# PG03_SHEET1.net
KiCad netlist of a schematic drawn in Altium Designer
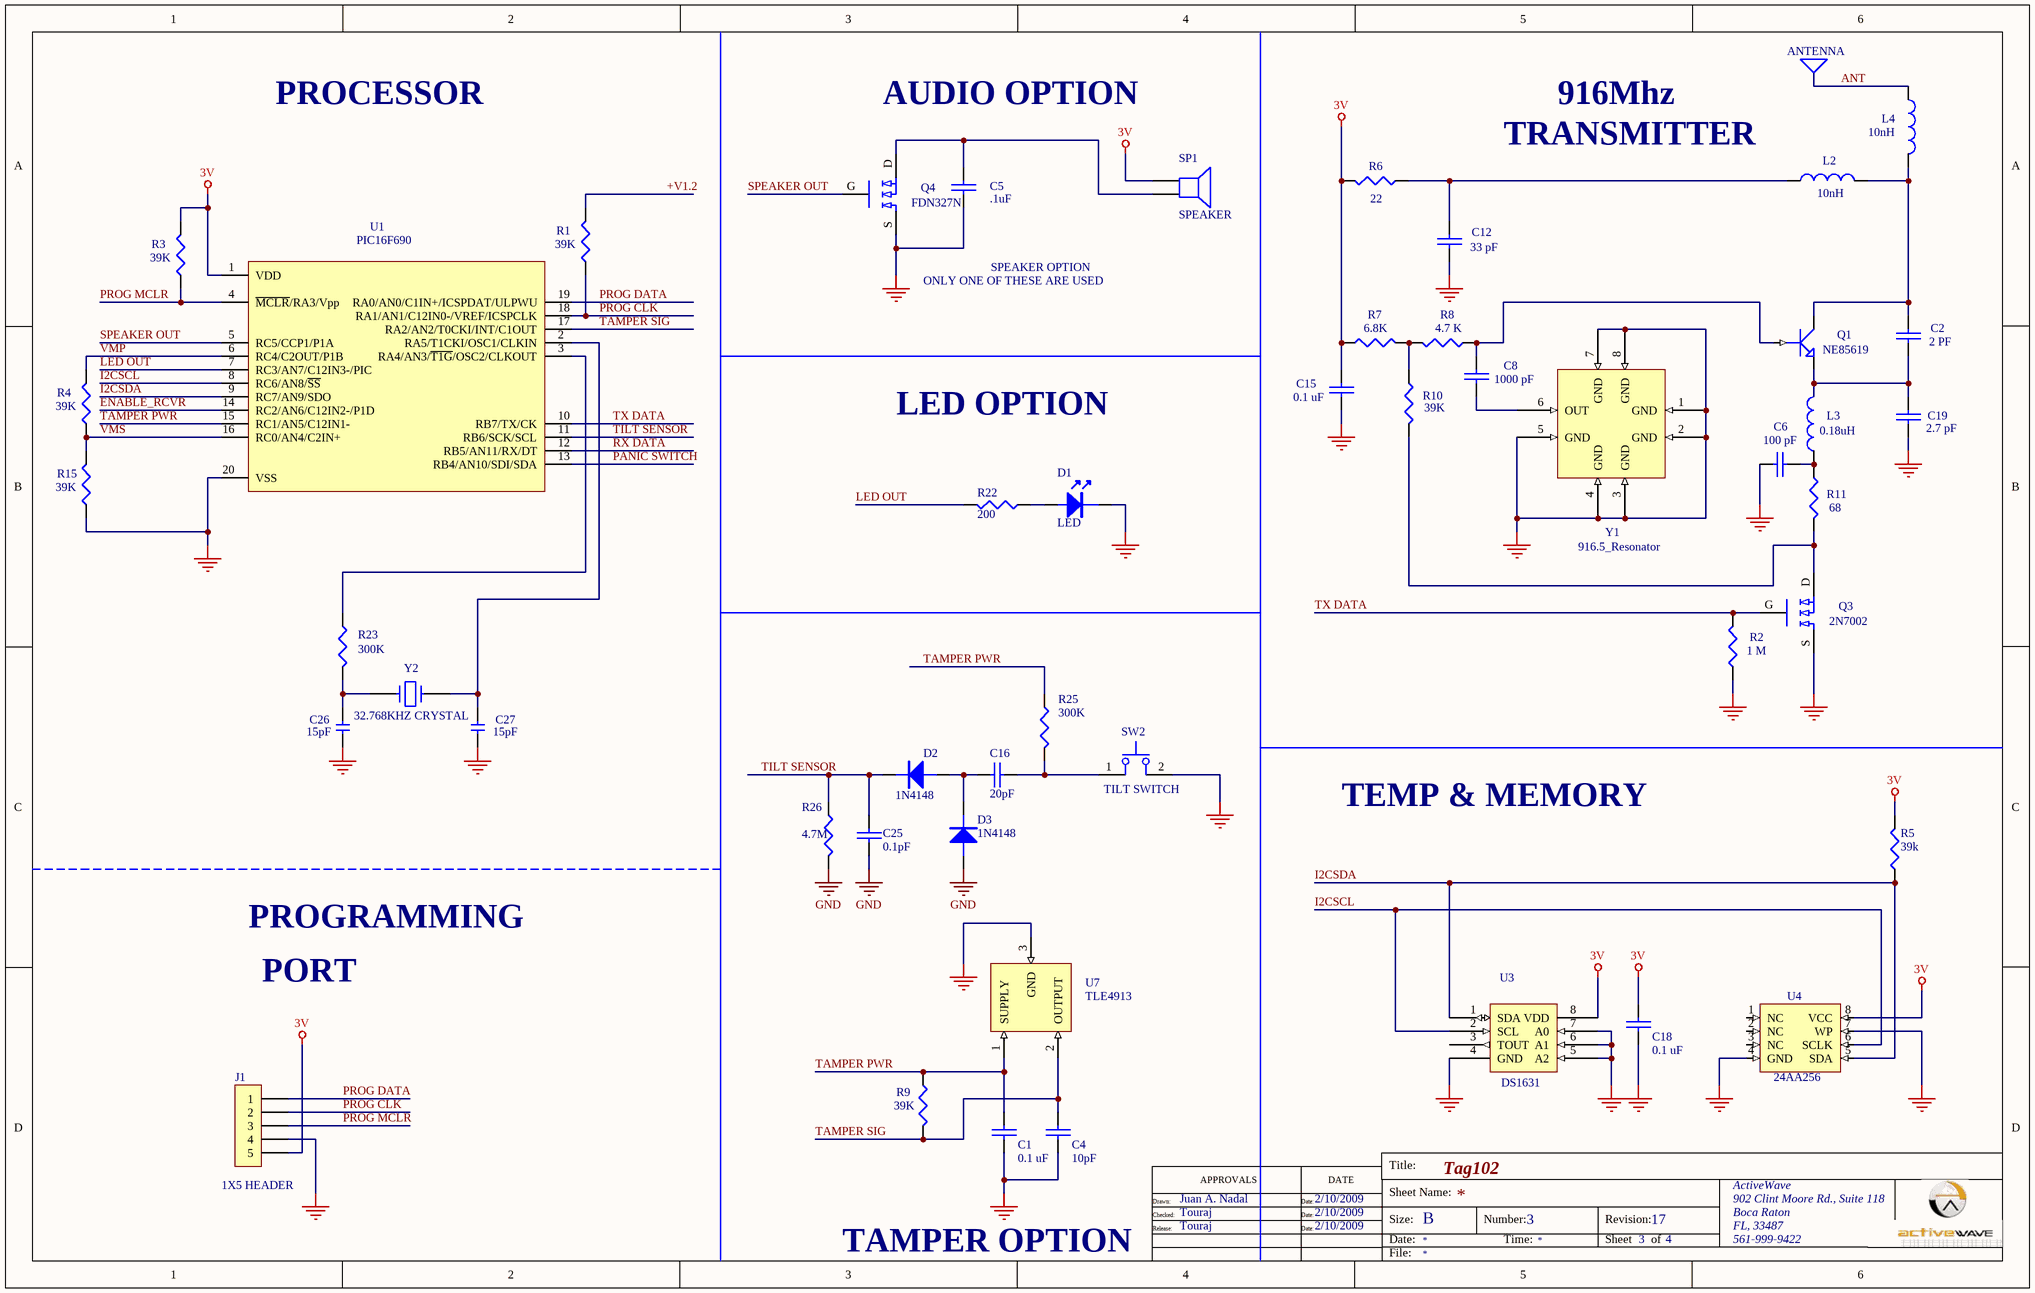
[diagram p0: PG03 SHEET1.schdoc]

(export (version "E")
  (design (tool "Eeschema 10.0.6"))
  (components
    (comp (ref "C1")
      (value "0.1 uF")
      (footprint "0603")
      (description "Capacitor")
      (libsource (lib "*") (part "CAP"))
    )
    (comp (ref "C2")
      (value "2 PF")
      (footprint "0603")
      (description "Capacitor")
      (libsource (lib "*") (part "CAP"))
    )
    (comp (ref "C4")
      (value "10pF")
      (footprint "0603")
      (description "Capacitor")
      (libsource (lib "*") (part "CAP"))
    )
    (comp (ref "C5")
      (value ".1uF")
      (footprint "0603")
      (description "Capacitor")
      (libsource (lib "*") (part "CAP"))
    )
    (comp (ref "C6")
      (value "100 pF")
      (footprint "0603")
      (description "Capacitor")
      (libsource (lib "*") (part "CAP"))
    )
    (comp (ref "C8")
      (value "1000 pF")
      (footprint "0603")
      (description "Capacitor")
      (libsource (lib "*") (part "CAP"))
    )
    (comp (ref "C12")
      (value "33 pF")
      (footprint "0603")
      (description "Capacitor")
      (libsource (lib "*") (part "CAP"))
    )
    (comp (ref "C15")
      (value "0.1 uF")
      (footprint "0603")
      (description "Capacitor")
      (libsource (lib "*") (part "CAP"))
    )
    (comp (ref "C16")
      (value "20pF")
      (footprint "0603")
      (description "Capacitor")
      (libsource (lib "*") (part "CAP"))
    )
    (comp (ref "C18")
      (value "0.1 uF")
      (footprint "0603")
      (description "Capacitor")
      (libsource (lib "*") (part "CAP"))
    )
    (comp (ref "C19")
      (value "2.7 pF")
      (footprint "0603")
      (description "Capacitor")
      (libsource (lib "*") (part "CAP"))
    )
    (comp (ref "C25")
      (value "0.1pF")
      (footprint "0603")
      (description "Capacitor")
      (libsource (lib "*") (part "CAP"))
    )
    (comp (ref "C26") (value "15pF") (footprint "0603") (libsource (lib "*") (part "C")))
    (comp (ref "C27") (value "15pF") (footprint "0603") (libsource (lib "*") (part "C")))
    (comp (ref "D1") (value "LED") (footprint "LED STANLEY H_1105W") (libsource (lib "*") (part "LED")))
    (comp (ref "D2")
      (value "1N4148")
      (footprint "sod123_021405")
      (description "Diode")
      (libsource (lib "*") (part "DIODE"))
    )
    (comp (ref "D3")
      (value "1N4148")
      (footprint "sod123_021405")
      (description "Diode")
      (libsource (lib "*") (part "DIODE"))
    )
    (comp (ref "J1")
      (value "1X5 HEADER")
      (footprint "1X5 HEADER")
      (description "Connector")
      (libsource (lib "*") (part "CON5"))
    )
    (comp (ref "L2") (value "10nH") (footprint "0603") (libsource (lib "*") (part "INDUCTOR")))
    (comp (ref "L3") (value "0.18uH") (footprint "0603") (libsource (lib "*") (part "INDUCTOR")))
    (comp (ref "L4") (value "10nH") (footprint "0603") (libsource (lib "*") (part "INDUCTOR")))
    (comp (ref "Q1")
      (value "NE85619")
      (footprint "3 PIN ULTRA SUPER MINI MOLD")
      (description "NPN Transistor")
      (libsource (lib "*") (part "NPN1"))
    )
    (comp (ref "Q3") (value "2N7002") (libsource (lib "*") (part "FET 2")))
    (comp (ref "Q4") (value "FDN327N") (libsource (lib "*") (part "FET 2")))
    (comp (ref "R1") (value "39K") (footprint "0603") (libsource (lib "*") (part "RESISTOR")))
    (comp (ref "R2") (value "1 M") (footprint "0603") (libsource (lib "*") (part "RESISTOR")))
    (comp (ref "R3") (value "39K") (footprint "0603") (libsource (lib "*") (part "RESISTOR")))
    (comp (ref "R4") (value "39K") (footprint "0603") (libsource (lib "*") (part "RESISTOR")))
    (comp (ref "R5") (value "39k") (footprint "0603") (libsource (lib "*") (part "RESISTOR")))
    (comp (ref "R6") (value "22") (footprint "0603") (libsource (lib "*") (part "RESISTOR")))
    (comp (ref "R7") (value "6.8K") (footprint "0603") (libsource (lib "*") (part "RESISTOR")))
    (comp (ref "R8") (value "4.7 K") (footprint "0603") (libsource (lib "*") (part "RESISTOR")))
    (comp (ref "R9") (value "39K") (footprint "0603") (libsource (lib "*") (part "RESISTOR")))
    (comp (ref "R10") (value "39K") (footprint "0603") (libsource (lib "*") (part "RESISTOR")))
    (comp (ref "R11") (value "68") (footprint "0603") (libsource (lib "*") (part "RES1")))
    (comp (ref "R15") (value "39K") (footprint "0603") (libsource (lib "*") (part "RESISTOR")))
    (comp (ref "R22") (value "200") (footprint "0603") (libsource (lib "*") (part "RES1")))
    (comp (ref "R23") (value "300K") (footprint "0603") (libsource (lib "*") (part "RESISTOR")))
    (comp (ref "R25") (value "300K") (footprint "0603") (libsource (lib "*") (part "RESISTOR")))
    (comp (ref "R26") (value "4.7M") (footprint "0603") (libsource (lib "*") (part "RESISTOR")))
    (comp (ref "SP1") (value "SPEAKER") (footprint "SMT_1028-S-R") (libsource (lib "*") (part "SPEAKER")))
    (comp (ref "SW2")
      (value "TILT SWITCH")
      (footprint "SQ-SEN-200")
      (libsource (lib "Common") (part "SWITCH PB"))
    )
    (comp (ref "U1") (value "PIC16F690") (libsource (lib "*") (part "PIC16F690")))
    (comp (ref "U3") (value "DS1631") (footprint "SO8 SMALL") (libsource (lib "*") (part "DS1631")))
    (comp (ref "U4") (value "24AA256") (footprint "SO8") (libsource (lib "*") (part "24AA256")))
    (comp (ref "U7") (value "TLE4913") (footprint "SOT23W") (libsource (lib "*") (part "HALL EFFECT SWITCH")))
    (comp (ref "Y1")
      (value "916.5_Resonator")
      (footprint "RESONATOR")
      (libsource (lib "*") (part "RESONATOR"))
    )
    (comp (ref "Y2")
      (value "32.768KHZ CRYSTAL")
      (footprint "CRYSTAL ABRACON ABS07")
      (description "Crystal")
      (libsource (lib "*") (part "CRYSTAL"))
    )
  )
  (nets
    (net (code "1") (name "/+V1.2") (class "Default")
      (node (ref "R1") (pin "2") (pinfunction "2_2") (pintype "passive"))
    )
    (net (code "2") (name "/ANT") (class "Default")
      (node (ref "L4") (pin "1") (pinfunction "1_1") (pintype "passive"))
    )
    (net (code "3") (name "/ENABLE_RCVR") (class "Default")
      (node (ref "U1") (pin "14") (pinfunction "RC2/AN6/C12IN2-/P1D_14") (pintype "passive"))
    )
    (net (code "4") (name "/I2CSCL") (class "Default")
      (node (ref "U1") (pin "8") (pinfunction "RC6/AN8/~{SS}_8") (pintype "passive"))
      (node (ref "U3") (pin "2") (pinfunction "SCL_2") (pintype "input"))
      (node (ref "U4") (pin "6") (pinfunction "SCLK_6") (pintype "input"))
    )
    (net (code "5") (name "/I2CSDA") (class "Default")
      (node (ref "R5") (pin "1") (pinfunction "1_1") (pintype "passive"))
      (node (ref "U1") (pin "9") (pinfunction "RC7/AN9/SDO_9") (pintype "passive"))
      (node (ref "U3") (pin "1") (pinfunction "SDA_1") (pintype "bidirectional"))
      (node (ref "U4") (pin "5") (pinfunction "SDA_5") (pintype "input"))
    )
    (net (code "6") (name "/LED OUT") (class "Default")
      (node (ref "R22") (pin "2") (pinfunction "2_2") (pintype "passive"))
      (node (ref "U1") (pin "7") (pinfunction "RC3/AN7/C12IN3-/PIC_7") (pintype "passive"))
    )
    (net (code "7") (name "/PANIC SWITCH") (class "Default")
      (node (ref "U1") (pin "13") (pinfunction "RB4/AN10/SDI/SDA_13") (pintype "passive"))
    )
    (net (code "8") (name "/PROG CLK") (class "Default")
      (node (ref "J1") (pin "2") (pinfunction "2_2") (pintype "passive"))
      (node (ref "R1") (pin "1") (pinfunction "1_1") (pintype "passive"))
      (node (ref "U1") (pin "18") (pinfunction "RA1/AN1/C12IN0-/VREF/ICSPCLK_18") (pintype "passive"))
    )
    (net (code "9") (name "/PROG DATA") (class "Default")
      (node (ref "J1") (pin "1") (pinfunction "1_1") (pintype "passive"))
      (node (ref "U1") (pin "19") (pinfunction "RA0/AN0/C1IN+/ICSPDAT/ULPWU_19") (pintype "passive"))
    )
    (net (code "10") (name "/PROG MCLR") (class "Default")
      (node (ref "J1") (pin "3") (pinfunction "3_3") (pintype "passive"))
      (node (ref "R3") (pin "1") (pinfunction "1_1") (pintype "passive"))
      (node (ref "U1") (pin "4") (pinfunction "~{MCLR}/RA3/Vpp_4") (pintype "passive"))
    )
    (net (code "11") (name "/RX DATA") (class "Default")
      (node (ref "U1") (pin "12") (pinfunction "RB5/AN11/RX/DT_12") (pintype "passive"))
    )
    (net (code "12") (name "/SPEAKER OUT") (class "Default")
      (node (ref "Q4") (pin "G") (pinfunction "G_G") (pintype "passive"))
      (node (ref "U1") (pin "5") (pinfunction "RC5/CCP1/P1A_5") (pintype "passive"))
    )
    (net (code "13") (name "/TAMPER PWR") (class "Default")
      (node (ref "C1") (pin "1") (pinfunction "1_1") (pintype "passive"))
      (node (ref "R25") (pin "1") (pinfunction "1_1") (pintype "passive"))
      (node (ref "R9") (pin "1") (pinfunction "1_1") (pintype "passive"))
      (node (ref "U1") (pin "15") (pinfunction "RC1/AN5/C12IN1-_15") (pintype "passive"))
      (node (ref "U7") (pin "1") (pinfunction "SUPPLY_1") (pintype "input"))
    )
    (net (code "14") (name "/TAMPER SIG") (class "Default")
      (node (ref "C4") (pin "1") (pinfunction "1_1") (pintype "passive"))
      (node (ref "R9") (pin "2") (pinfunction "2_2") (pintype "passive"))
      (node (ref "U1") (pin "17") (pinfunction "RA2/AN2/T0CKI/INT/C1OUT_17") (pintype "passive"))
      (node (ref "U7") (pin "2") (pinfunction "OUTPUT_2") (pintype "input"))
    )
    (net (code "15") (name "/TILT SENSOR") (class "Default")
      (node (ref "C25") (pin "1") (pinfunction "1_1") (pintype "passive"))
      (node (ref "D2") (pin "K") (pinfunction "K_K") (pintype "passive"))
      (node (ref "R26") (pin "1") (pinfunction "1_1") (pintype "passive"))
      (node (ref "U1") (pin "11") (pinfunction "RB6/SCK/SCL_11") (pintype "passive"))
    )
    (net (code "16") (name "/TX DATA") (class "Default")
      (node (ref "Q3") (pin "G") (pinfunction "G_G") (pintype "passive"))
      (node (ref "R2") (pin "2") (pinfunction "2_2") (pintype "passive"))
      (node (ref "U1") (pin "10") (pinfunction "RB7/TX/CK_10") (pintype "passive"))
    )
    (net (code "17") (name "/VMP") (class "Default")
      (node (ref "R4") (pin "2") (pinfunction "2_2") (pintype "passive"))
      (node (ref "U1") (pin "6") (pinfunction "RC4/C2OUT/P1B_6") (pintype "passive"))
    )
    (net (code "18") (name "/VMS") (class "Default")
      (node (ref "R15") (pin "2") (pinfunction "2_2") (pintype "passive"))
      (node (ref "R4") (pin "1") (pinfunction "1_1") (pintype "passive"))
      (node (ref "U1") (pin "16") (pinfunction "RC0/AN4/C2IN+_16") (pintype "passive"))
    )
    (net (code "19") (name "3V") (class "Default")
      (node (ref "C15") (pin "1") (pinfunction "1_1") (pintype "passive"))
      (node (ref "C18") (pin "1") (pinfunction "1_1") (pintype "passive"))
      (node (ref "J1") (pin "5") (pinfunction "5_5") (pintype "passive"))
      (node (ref "R3") (pin "2") (pinfunction "2_2") (pintype "passive"))
      (node (ref "R5") (pin "2") (pinfunction "2_2") (pintype "passive"))
      (node (ref "R6") (pin "2") (pinfunction "2_2") (pintype "passive"))
      (node (ref "R7") (pin "1") (pinfunction "1_1") (pintype "passive"))
      (node (ref "SP1") (pin "1") (pinfunction "1_1") (pintype "passive"))
      (node (ref "U1") (pin "1") (pinfunction "VDD_1") (pintype "passive"))
      (node (ref "U3") (pin "8") (pinfunction "VDD_8") (pintype "power_in"))
      (node (ref "U4") (pin "8") (pinfunction "VCC_8") (pintype "input"))
    )
    (net (code "20") (name "GND") (class "Default")
      (node (ref "C1") (pin "2") (pinfunction "2_2") (pintype "passive"))
      (node (ref "C12") (pin "2") (pinfunction "2_2") (pintype "passive"))
      (node (ref "C15") (pin "2") (pinfunction "2_2") (pintype "passive"))
      (node (ref "C18") (pin "2") (pinfunction "2_2") (pintype "passive"))
      (node (ref "C19") (pin "2") (pinfunction "2_2") (pintype "passive"))
      (node (ref "C25") (pin "2") (pinfunction "2_2") (pintype "passive"))
      (node (ref "C26") (pin "1") (pinfunction "1_1") (pintype "passive"))
      (node (ref "C27") (pin "1") (pinfunction "1_1") (pintype "passive"))
      (node (ref "C4") (pin "2") (pinfunction "2_2") (pintype "passive"))
      (node (ref "C5") (pin "2") (pinfunction "2_2") (pintype "passive"))
      (node (ref "C6") (pin "1") (pinfunction "1_1") (pintype "passive"))
      (node (ref "D1") (pin "K") (pinfunction "K_K") (pintype "passive"))
      (node (ref "D3") (pin "A") (pinfunction "A_A") (pintype "passive"))
      (node (ref "J1") (pin "4") (pinfunction "4_4") (pintype "passive"))
      (node (ref "Q3") (pin "S") (pinfunction "S_S") (pintype "passive"))
      (node (ref "Q4") (pin "S") (pinfunction "S_S") (pintype "passive"))
      (node (ref "R15") (pin "1") (pinfunction "1_1") (pintype "passive"))
      (node (ref "R2") (pin "1") (pinfunction "1_1") (pintype "passive"))
      (node (ref "R26") (pin "2") (pinfunction "2_2") (pintype "passive"))
      (node (ref "SW2") (pin "2") (pinfunction "2_2") (pintype "passive"))
      (node (ref "U1") (pin "20") (pinfunction "VSS_20") (pintype "passive"))
      (node (ref "U3") (pin "4") (pinfunction "GND_4") (pintype "power_in"))
      (node (ref "U3") (pin "5") (pinfunction "A2_5") (pintype "input"))
      (node (ref "U3") (pin "6") (pinfunction "A1_6") (pintype "input"))
      (node (ref "U3") (pin "7") (pinfunction "A0_7") (pintype "input"))
      (node (ref "U4") (pin "4") (pinfunction "GND_4") (pintype "input"))
      (node (ref "U4") (pin "7") (pinfunction "WP_7") (pintype "input"))
      (node (ref "U7") (pin "3") (pinfunction "GND_3") (pintype "input"))
      (node (ref "Y1") (pin "1") (pinfunction "GND_1") (pintype "input"))
      (node (ref "Y1") (pin "2") (pinfunction "GND_2") (pintype "input"))
      (node (ref "Y1") (pin "3") (pinfunction "GND_3") (pintype "input"))
      (node (ref "Y1") (pin "4") (pinfunction "GND_4") (pintype "input"))
      (node (ref "Y1") (pin "5") (pinfunction "GND_5") (pintype "input"))
      (node (ref "Y1") (pin "7") (pinfunction "GND_7") (pintype "input"))
      (node (ref "Y1") (pin "8") (pinfunction "GND_8") (pintype "input"))
    )
    (net (code "21") (name "Net-(C2-Pad1)") (class "Default")
      (node (ref "C2") (pin "1") (pinfunction "1_1") (pintype "passive"))
      (node (ref "L2") (pin "2") (pinfunction "2_2") (pintype "passive"))
      (node (ref "L4") (pin "2") (pinfunction "2_2") (pintype "passive"))
      (node (ref "Q1") (pin "C") (pinfunction "C_C") (pintype "passive"))
    )
    (net (code "22") (name "Net-(C5-Pad1)") (class "Default")
      (node (ref "C5") (pin "1") (pinfunction "1_1") (pintype "passive"))
      (node (ref "Q4") (pin "D") (pinfunction "D_D") (pintype "passive"))
      (node (ref "SP1") (pin "2") (pinfunction "2_2") (pintype "passive"))
    )
    (net (code "23") (name "Net-(C6-Pad2)") (class "Default")
      (node (ref "C6") (pin "2") (pinfunction "2_2") (pintype "passive"))
      (node (ref "L3") (pin "1") (pinfunction "1_1") (pintype "passive"))
      (node (ref "R11") (pin "1") (pinfunction "1_1") (pintype "passive"))
    )
    (net (code "24") (name "Net-(C8-Pad1)") (class "Default")
      (node (ref "C8") (pin "1") (pinfunction "1_1") (pintype "passive"))
      (node (ref "Q1") (pin "B") (pinfunction "B_B") (pintype "input"))
      (node (ref "R8") (pin "1") (pinfunction "1_1") (pintype "passive"))
    )
    (net (code "25") (name "Net-(C12-Pad1)") (class "Default")
      (node (ref "C12") (pin "1") (pinfunction "1_1") (pintype "passive"))
      (node (ref "L2") (pin "1") (pinfunction "1_1") (pintype "passive"))
      (node (ref "R6") (pin "1") (pinfunction "1_1") (pintype "passive"))
    )
    (net (code "26") (name "Net-(C16-Pad1)") (class "Default")
      (node (ref "C16") (pin "1") (pinfunction "1_1") (pintype "passive"))
      (node (ref "D2") (pin "A") (pinfunction "A_A") (pintype "passive"))
      (node (ref "D3") (pin "K") (pinfunction "K_K") (pintype "passive"))
    )
    (net (code "27") (name "Net-(C16-Pad2)") (class "Default")
      (node (ref "C16") (pin "2") (pinfunction "2_2") (pintype "passive"))
      (node (ref "R25") (pin "2") (pinfunction "2_2") (pintype "passive"))
      (node (ref "SW2") (pin "1") (pinfunction "1_1") (pintype "passive"))
    )
    (net (code "28") (name "Net-(C19-Pad1)") (class "Default")
      (node (ref "C19") (pin "1") (pinfunction "1_1") (pintype "passive"))
      (node (ref "C2") (pin "2") (pinfunction "2_2") (pintype "passive"))
      (node (ref "L3") (pin "2") (pinfunction "2_2") (pintype "passive"))
      (node (ref "Q1") (pin "E") (pinfunction "E_E") (pintype "passive"))
    )
    (net (code "29") (name "Net-(C26-Pad2)") (class "Default")
      (node (ref "C26") (pin "2") (pinfunction "2_2") (pintype "passive"))
      (node (ref "R23") (pin "2") (pinfunction "2_2") (pintype "passive"))
      (node (ref "Y2") (pin "2") (pinfunction "2_2") (pintype "passive"))
    )
    (net (code "30") (name "Net-(D1-PadA)") (class "Default")
      (node (ref "D1") (pin "A") (pinfunction "A_A") (pintype "passive"))
      (node (ref "R22") (pin "1") (pinfunction "1_1") (pintype "passive"))
    )
    (net (code "31") (name "Net-(Q3-PadD)") (class "Default")
      (node (ref "Q3") (pin "D") (pinfunction "D_D") (pintype "passive"))
      (node (ref "R10") (pin "2") (pinfunction "2_2") (pintype "passive"))
      (node (ref "R11") (pin "2") (pinfunction "2_2") (pintype "passive"))
    )
    (net (code "32") (name "Net-(R10-Pad1)") (class "Default")
      (node (ref "R10") (pin "1") (pinfunction "1_1") (pintype "passive"))
      (node (ref "R7") (pin "2") (pinfunction "2_2") (pintype "passive"))
      (node (ref "R8") (pin "2") (pinfunction "2_2") (pintype "passive"))
    )
    (net (code "33") (name "Net-(U1-RA4{slash}AN3{slash}~{T1G}{slash}OSC2{slash}CLKOUT)") (class "Default")
      (node (ref "R23") (pin "1") (pinfunction "1_1") (pintype "passive"))
      (node (ref "U1") (pin "3") (pinfunction "RA4/AN3/~{T1G}/OSC2/CLKOUT_3") (pintype "passive"))
    )
    (net (code "34") (name "Net-(U1-RA5{slash}T1CKI{slash}OSC1{slash}CLKIN)") (class "Default")
      (node (ref "C27") (pin "2") (pinfunction "2_2") (pintype "passive"))
      (node (ref "U1") (pin "2") (pinfunction "RA5/T1CKI/OSC1/CLKIN_2") (pintype "passive"))
      (node (ref "Y2") (pin "1") (pinfunction "1_1") (pintype "passive"))
    )
    (net (code "35") (name "Net-(Y1-OUT)") (class "Default")
      (node (ref "C8") (pin "2") (pinfunction "2_2") (pintype "passive"))
      (node (ref "Y1") (pin "6") (pinfunction "OUT_6") (pintype "input"))
    )
    (net (code "36") (name "unconnected-(U3-TOUT-Pad3)") (class "Default")
      (node (ref "U3") (pin "3") (pinfunction "TOUT_3") (pintype "output"))
    )
    (net (code "37") (name "unconnected-(U4-NC-Pad1)") (class "Default")
      (node (ref "U4") (pin "1") (pinfunction "NC_1") (pintype "input"))
    )
    (net (code "38") (name "unconnected-(U4-NC-Pad2)") (class "Default")
      (node (ref "U4") (pin "2") (pinfunction "NC_2") (pintype "input"))
    )
    (net (code "39") (name "unconnected-(U4-NC-Pad3)") (class "Default")
      (node (ref "U4") (pin "3") (pinfunction "NC_3") (pintype "input"))
    )
  )
)
